# cdh.net
KiCad netlist of a schematic drawn in Altium Designer
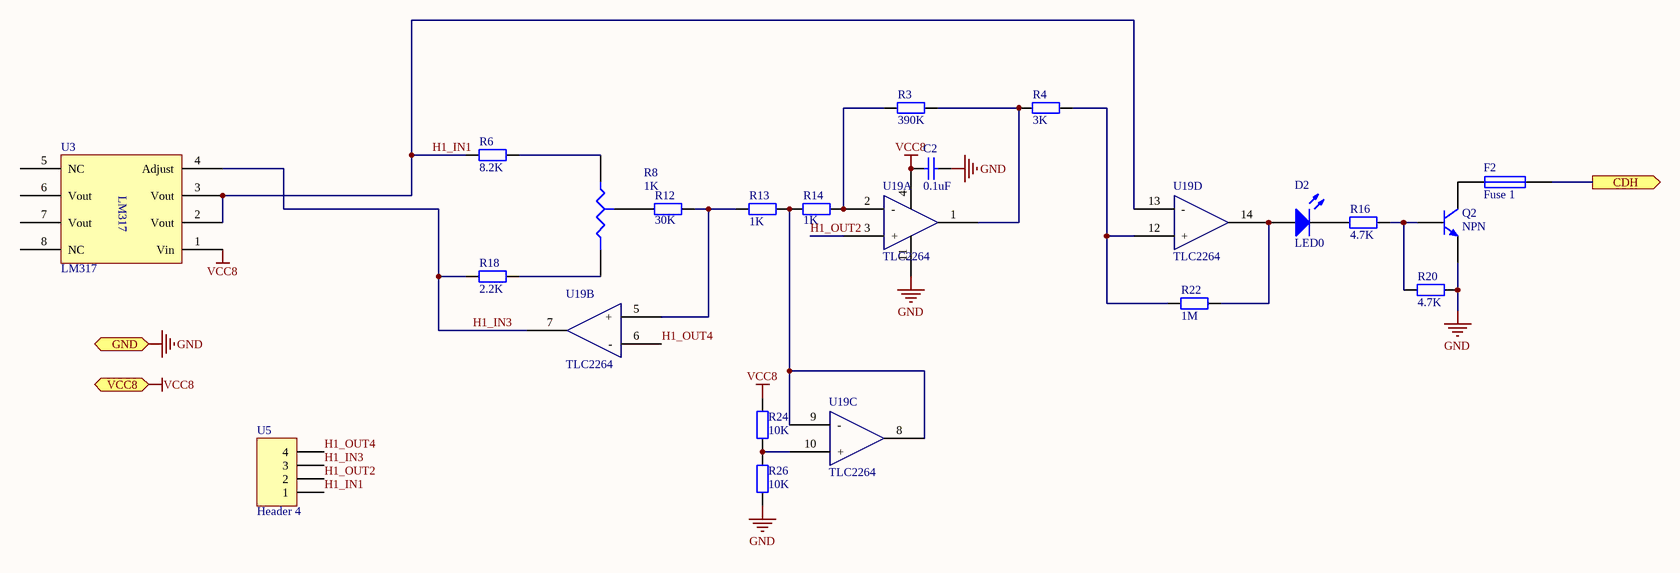
[diagram p0: cdh.SchDoc]

(export (version "E")
  (design (tool "Eeschema 10.0.6"))
  (components
    (comp (ref "C2")
      (value "0.1uF")
      (footprint "C0805")
      (description "Capacitor (Semiconductor SIM Model)")
      (fields (field (name "Comment") "Cap Semi") (field (name "PUBLISHER") "Altium Limited"))
      (libsource (lib "Miscellaneous Devices") (part "Cap Semi"))
    )
    (comp (ref "D2")
      (value "LED0")
      (footprint "LED1")
      (description "Typical INFRARED GaAs LED")
      (fields (field (name "PUBLISHER") "Altium Limited"))
      (libsource (lib "Miscellaneous Devices") (part "LED0"))
    )
    (comp (ref "F2")
      (value "Fuse 1")
      (footprint "1206")
      (description "Fuse")
      (fields (field (name "PUBLISHER") "Altium Limited"))
      (libsource (lib "Miscellaneous Devices") (part "Fuse 1"))
    )
    (comp (ref "Q2")
      (value "NPN")
      (footprint "SOT-23")
      (description "NPN Bipolar Transistor")
      (fields (field (name "PUBLISHER") "Altium Limited"))
      (libsource (lib "Miscellaneous Devices") (part "NPN"))
    )
    (comp (ref "R3")
      (value "390K")
      (footprint "0805")
      (description "Resistor")
      (fields (field (name "Comment") "Res2") (field (name "PUBLISHER") "Altium Limited"))
      (libsource (lib "Miscellaneous Devices") (part "Res2"))
    )
    (comp (ref "R4")
      (value "3K")
      (footprint "0805")
      (description "Resistor")
      (fields (field (name "Comment") "Res2") (field (name "PUBLISHER") "Altium Limited"))
      (libsource (lib "Miscellaneous Devices") (part "Res2"))
    )
    (comp (ref "R6")
      (value "8.2K")
      (footprint "0805")
      (description "Resistor")
      (fields (field (name "Comment") "Res2") (field (name "PUBLISHER") "Altium Limited"))
      (libsource (lib "Miscellaneous Devices") (part "Res2"))
    )
    (comp (ref "R8")
      (value "1K")
      (footprint "3224W")
      (description "Tapped Resistor")
      (fields (field (name "Comment") "Res Tap") (field (name "PUBLISHER") "Altium Limited"))
      (libsource (lib "Miscellaneous Devices") (part "Res Tap"))
    )
    (comp (ref "R12")
      (value "30K")
      (footprint "0805")
      (description "Resistor")
      (fields (field (name "Comment") "Res2") (field (name "PUBLISHER") "Altium Limited"))
      (libsource (lib "Miscellaneous Devices") (part "Res2"))
    )
    (comp (ref "R13")
      (value "1K")
      (footprint "0805")
      (description "Resistor")
      (fields (field (name "Comment") "Res2") (field (name "PUBLISHER") "Altium Limited"))
      (libsource (lib "Miscellaneous Devices") (part "Res2"))
    )
    (comp (ref "R14")
      (value "1K")
      (footprint "0805")
      (description "Resistor")
      (fields (field (name "Comment") "Res2") (field (name "PUBLISHER") "Altium Limited"))
      (libsource (lib "") (part "Res2_2"))
    )
    (comp (ref "R16")
      (value "4.7K")
      (footprint "0805")
      (description "Resistor")
      (fields (field (name "Comment") "Res2") (field (name "PUBLISHER") "Altium Limited"))
      (libsource (lib "Miscellaneous Devices") (part "Res2"))
    )
    (comp (ref "R18")
      (value "2.2K")
      (footprint "0805")
      (description "Resistor")
      (fields (field (name "Comment") "Res2") (field (name "PUBLISHER") "Altium Limited"))
      (libsource (lib "Miscellaneous Devices") (part "Res2"))
    )
    (comp (ref "R20")
      (value "4.7K")
      (footprint "0805")
      (description "Resistor")
      (fields (field (name "Comment") "Res2") (field (name "PUBLISHER") "Altium Limited"))
      (libsource (lib "Miscellaneous Devices") (part "Res2"))
    )
    (comp (ref "R22")
      (value "1M")
      (footprint "0805")
      (description "Resistor")
      (fields (field (name "Comment") "Res2") (field (name "PUBLISHER") "Altium Limited"))
      (libsource (lib "Miscellaneous Devices") (part "Res2"))
    )
    (comp (ref "R24")
      (value "10K")
      (footprint "0805")
      (description "Resistor")
      (fields (field (name "Comment") "Res2") (field (name "PUBLISHER") "Altium Limited"))
      (libsource (lib "") (part "Res2_1"))
    )
    (comp (ref "R26")
      (value "10K")
      (footprint "0805")
      (description "Resistor")
      (fields (field (name "Comment") "Res2") (field (name "PUBLISHER") "Altium Limited"))
      (libsource (lib "") (part "Res2_1"))
    )
    (comp (ref "U3") (value "LM317") (footprint "SO-8") (libsource (lib "磁导航") (part "LM317")))
    (comp (ref "U5")
      (value "Header 4")
      (footprint "PIN4")
      (description "Header, 4-Pin")
      (fields (field (name "PUBLISHER") "Altium Limited"))
      (libsource (lib "Miscellaneous Connectors") (part "Header 4"))
    )
    (comp (ref "U19") (value "TLC2264") (footprint "TSSOP14") (libsource (lib "EXPLORER") (part "TLC2264")))
  )
  (nets
    (net (code "1") (name "/CDH") (class "Default")
      (node (ref "F2") (pin "2") (pinfunction "2_2") (pintype "passive"))
    )
    (net (code "2") (name "/H1_IN1") (class "Default")
      (node (ref "R6") (pin "1") (pinfunction "1_1") (pintype "passive"))
      (node (ref "U19") (pin "13") (pinfunction "-_13") (pintype "passive"))
      (node (ref "U3") (pin "2") (pinfunction "Vout_2") (pintype "passive"))
      (node (ref "U3") (pin "3") (pinfunction "Vout_3") (pintype "passive"))
      (node (ref "U5") (pin "1") (pinfunction "1_1") (pintype "passive"))
    )
    (net (code "3") (name "/H1_IN3") (class "Default")
      (node (ref "R18") (pin "1") (pinfunction "1_1") (pintype "passive"))
      (node (ref "U19") (pin "7") (pinfunction "2OUT_7") (pintype "passive"))
      (node (ref "U3") (pin "4") (pinfunction "Adjust_4") (pintype "passive"))
      (node (ref "U5") (pin "3") (pinfunction "3_3") (pintype "passive"))
    )
    (net (code "4") (name "/H1_OUT2") (class "Default")
      (node (ref "U19") (pin "3") (pinfunction "+_3") (pintype "passive"))
      (node (ref "U5") (pin "2") (pinfunction "2_2") (pintype "passive"))
    )
    (net (code "5") (name "/H1_OUT4") (class "Default")
      (node (ref "U19") (pin "6") (pinfunction "-_6") (pintype "passive"))
      (node (ref "U5") (pin "4") (pinfunction "4_4") (pintype "passive"))
    )
    (net (code "6") (name "GND") (class "Default")
      (node (ref "C2") (pin "1") (pinfunction "1_1") (pintype "passive"))
      (node (ref "Q2") (pin "3") (pinfunction "E_3") (pintype "passive"))
      (node (ref "R20") (pin "2") (pinfunction "2_2") (pintype "passive"))
      (node (ref "R26") (pin "1") (pinfunction "1_1") (pintype "passive"))
      (node (ref "U19") (pin "11") (pinfunction "GND_11") (pintype "passive"))
    )
    (net (code "7") (name "Net-(D2-A)") (class "Default")
      (node (ref "D2") (pin "1") (pinfunction "A_1") (pintype "passive"))
      (node (ref "R22") (pin "2") (pinfunction "2_2") (pintype "passive"))
      (node (ref "U19") (pin "14") (pinfunction "4OUT_14") (pintype "passive"))
    )
    (net (code "8") (name "Net-(D2-K)") (class "Default")
      (node (ref "D2") (pin "2") (pinfunction "K_2") (pintype "passive"))
      (node (ref "R16") (pin "1") (pinfunction "1_1") (pintype "passive"))
    )
    (net (code "9") (name "Net-(Q2-B)") (class "Default")
      (node (ref "Q2") (pin "2") (pinfunction "B_2") (pintype "passive"))
      (node (ref "R16") (pin "2") (pinfunction "2_2") (pintype "passive"))
      (node (ref "R20") (pin "1") (pinfunction "1_1") (pintype "passive"))
    )
    (net (code "10") (name "Net-(Q2-C)") (class "Default")
      (node (ref "F2") (pin "1") (pinfunction "1_1") (pintype "passive"))
      (node (ref "Q2") (pin "1") (pinfunction "C_1") (pintype "passive"))
    )
    (net (code "11") (name "Net-(R8-A)") (class "Default")
      (node (ref "R6") (pin "2") (pinfunction "2_2") (pintype "passive"))
      (node (ref "R8") (pin "1") (pinfunction "A_1") (pintype "passive"))
    )
    (net (code "12") (name "Net-(R8-B)") (class "Default")
      (node (ref "R18") (pin "2") (pinfunction "2_2") (pintype "passive"))
      (node (ref "R8") (pin "2") (pinfunction "B_2") (pintype "passive"))
    )
    (net (code "13") (name "Net-(R8-TAP)") (class "Default")
      (node (ref "R12") (pin "1") (pinfunction "1_1") (pintype "passive"))
      (node (ref "R8") (pin "3") (pinfunction "TAP_3") (pintype "passive"))
    )
    (net (code "14") (name "Net-(U19A--)") (class "Default")
      (node (ref "R14") (pin "1") (pinfunction "1_1") (pintype "passive"))
      (node (ref "R3") (pin "1") (pinfunction "1_1") (pintype "passive"))
      (node (ref "U19") (pin "2") (pinfunction "-_2") (pintype "passive"))
    )
    (net (code "15") (name "Net-(U19A-1OUT)") (class "Default")
      (node (ref "R3") (pin "2") (pinfunction "2_2") (pintype "passive"))
      (node (ref "R4") (pin "1") (pinfunction "1_1") (pintype "passive"))
      (node (ref "U19") (pin "1") (pinfunction "1OUT_1") (pintype "passive"))
    )
    (net (code "16") (name "Net-(U19B-+)") (class "Default")
      (node (ref "R12") (pin "2") (pinfunction "2_2") (pintype "passive"))
      (node (ref "R13") (pin "1") (pinfunction "1_1") (pintype "passive"))
      (node (ref "U19") (pin "5") (pinfunction "+_5") (pintype "passive"))
    )
    (net (code "17") (name "Net-(U19C-+)") (class "Default")
      (node (ref "R24") (pin "1") (pinfunction "1_1") (pintype "passive"))
      (node (ref "R26") (pin "2") (pinfunction "2_2") (pintype "passive"))
      (node (ref "U19") (pin "10") (pinfunction "+_10") (pintype "passive"))
    )
    (net (code "18") (name "Net-(U19C--)") (class "Default")
      (node (ref "R13") (pin "2") (pinfunction "2_2") (pintype "passive"))
      (node (ref "R14") (pin "2") (pinfunction "2_2") (pintype "passive"))
      (node (ref "U19") (pin "8") (pinfunction "3OUT_8") (pintype "passive"))
      (node (ref "U19") (pin "9") (pinfunction "-_9") (pintype "passive"))
    )
    (net (code "19") (name "Net-(U19D-+)") (class "Default")
      (node (ref "R22") (pin "1") (pinfunction "1_1") (pintype "passive"))
      (node (ref "R4") (pin "2") (pinfunction "2_2") (pintype "passive"))
      (node (ref "U19") (pin "12") (pinfunction "+_12") (pintype "passive"))
    )
    (net (code "20") (name "VCC8") (class "Default")
      (node (ref "C2") (pin "2") (pinfunction "2_2") (pintype "passive"))
      (node (ref "R24") (pin "2") (pinfunction "2_2") (pintype "passive"))
      (node (ref "U19") (pin "4") (pinfunction "VCC_4") (pintype "passive"))
      (node (ref "U3") (pin "1") (pinfunction "Vin_1") (pintype "passive"))
    )
    (net (code "21") (name "unconnected-(U3-NC-Pad5)") (class "Default")
      (node (ref "U3") (pin "5") (pinfunction "NC_5") (pintype "passive"))
    )
    (net (code "22") (name "unconnected-(U3-NC-Pad8)") (class "Default")
      (node (ref "U3") (pin "8") (pinfunction "NC_8") (pintype "passive"))
    )
    (net (code "23") (name "unconnected-(U3-Vout-Pad6)") (class "Default")
      (node (ref "U3") (pin "6") (pinfunction "Vout_6") (pintype "passive"))
    )
    (net (code "24") (name "unconnected-(U3-Vout-Pad7)") (class "Default")
      (node (ref "U3") (pin "7") (pinfunction "Vout_7") (pintype "passive"))
    )
  )
)
